# PCIe_USB.net
KiCad netlist of a schematic drawn in Altium Designer
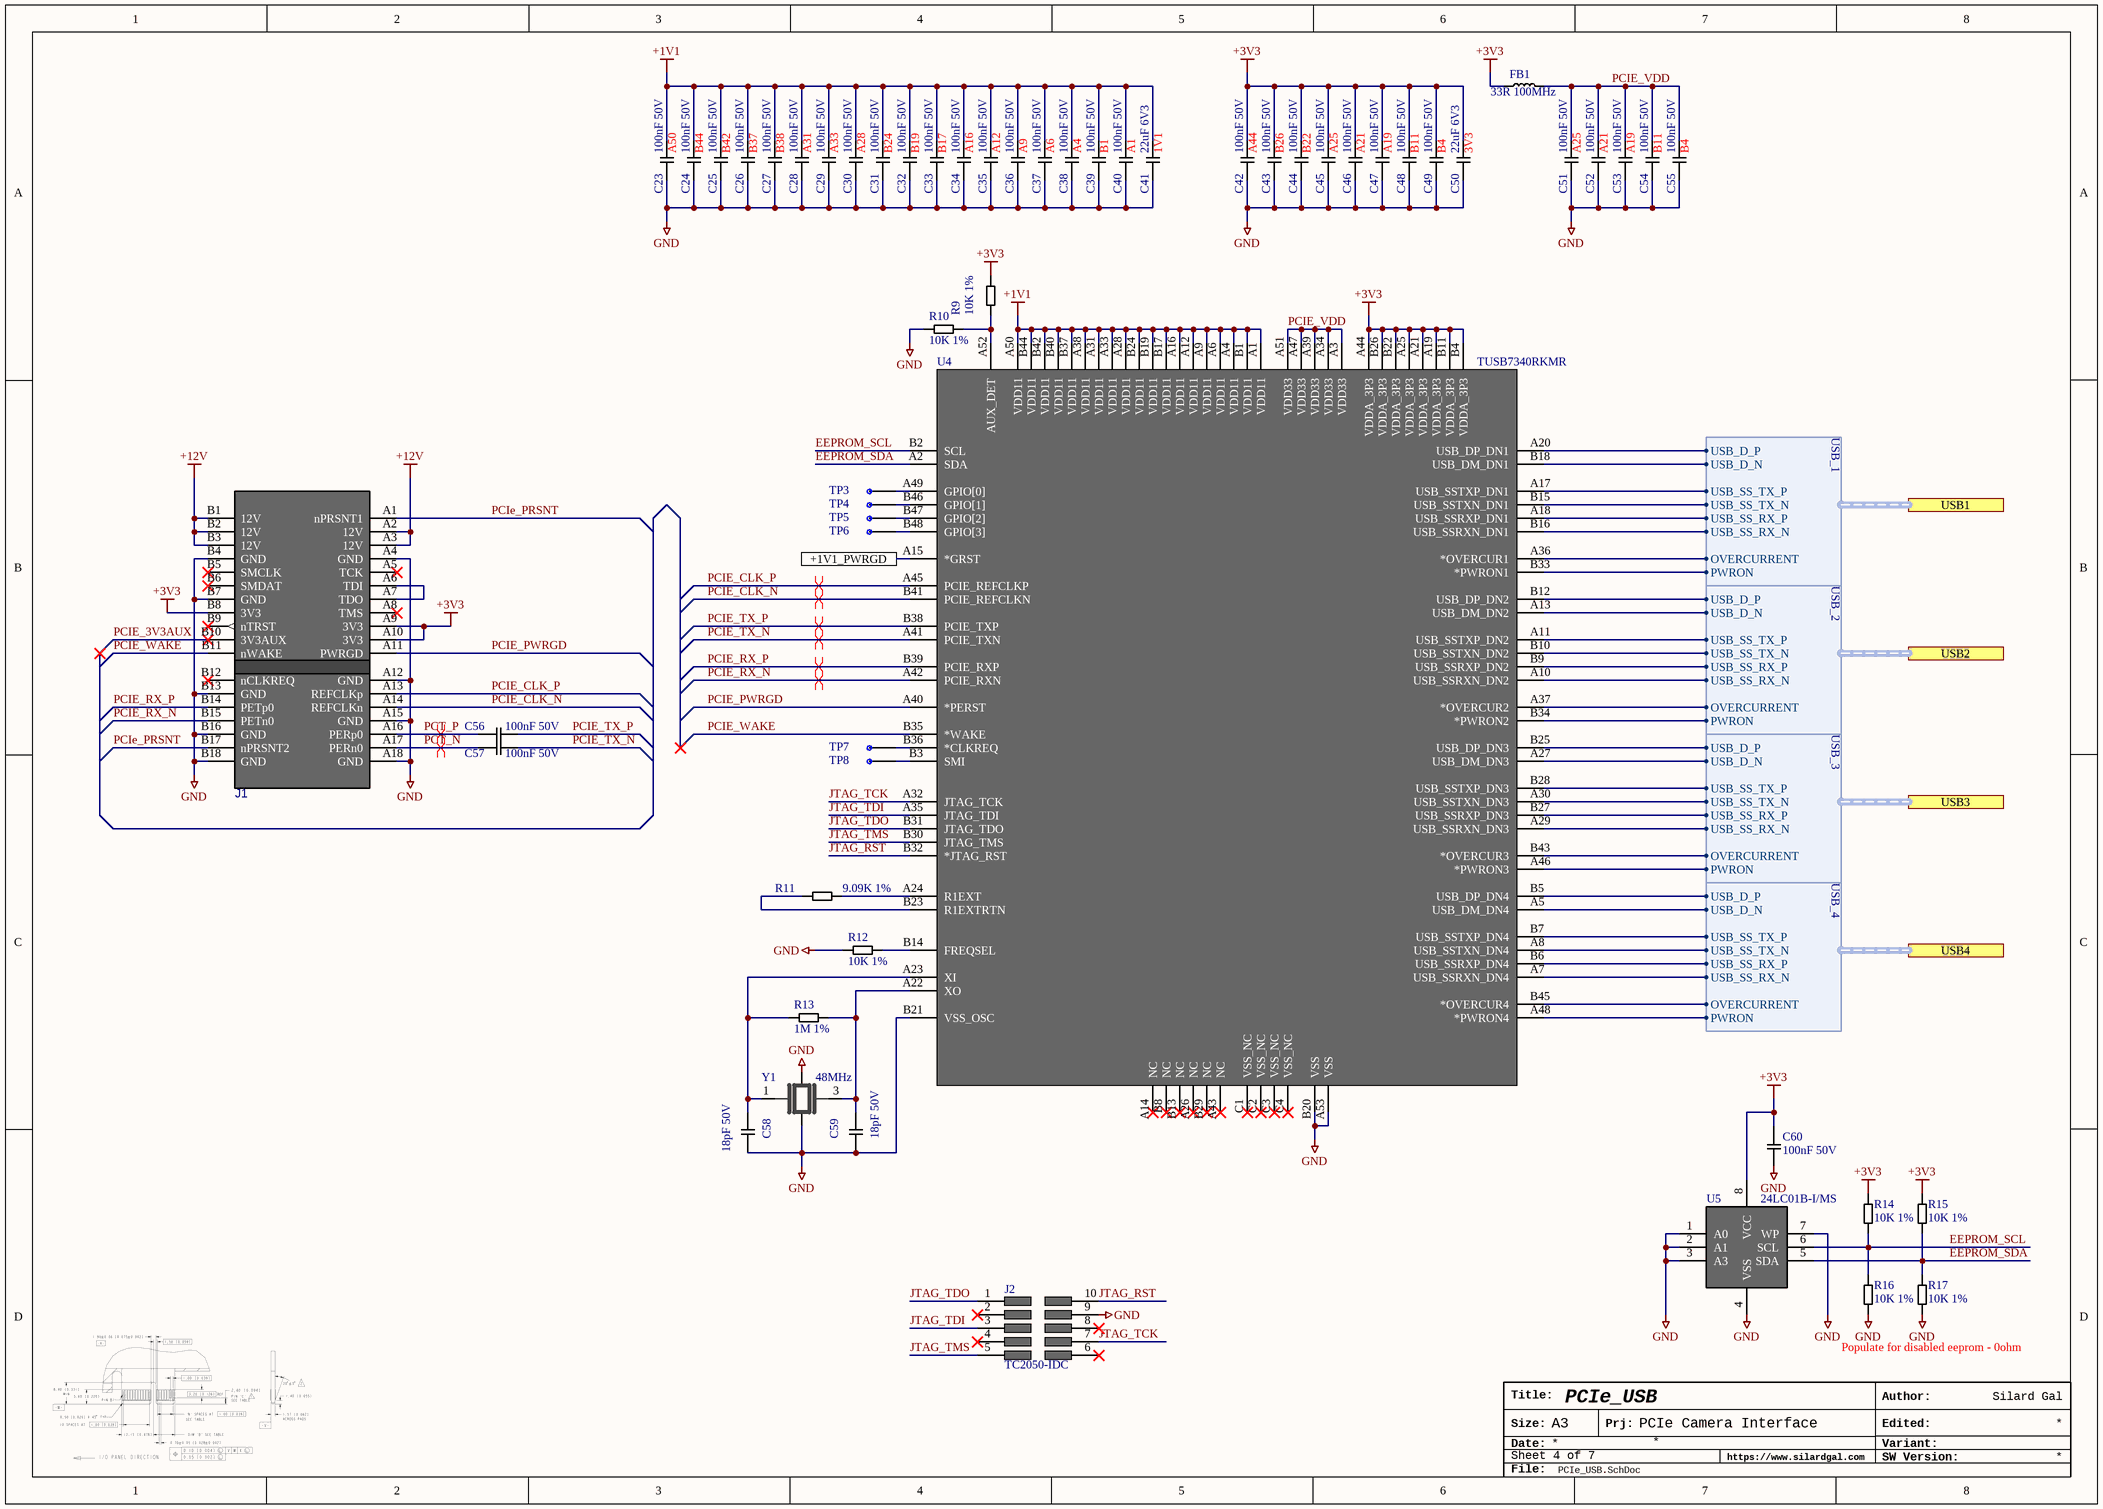
[diagram p0: PCIe_USB.SchDoc]

(export (version "E")
  (design (tool "Eeschema 10.0.6"))
  (components
    (comp (ref "C23")
      (value "100nF 50V")
      (footprint "CAPC1608X06N")
      (description "0.1 µF ±10% 50V Ceramic Capacitor X7R 0603 (1608 Metric)")
      (fields (field (name "MPN") "GCM188R71H104KA57D"))
      (libsource (lib "PCIe_Camera_Interface_Library") (part "100nF 50V"))
    )
    (comp (ref "C24")
      (value "100nF 50V")
      (footprint "CAPC1608X06N")
      (description "0.1 µF ±10% 50V Ceramic Capacitor X7R 0603 (1608 Metric)")
      (fields (field (name "MPN") "GCM188R71H104KA57D"))
      (libsource (lib "PCIe_Camera_Interface_Library") (part "100nF 50V"))
    )
    (comp (ref "C25")
      (value "100nF 50V")
      (footprint "CAPC1608X06N")
      (description "0.1 µF ±10% 50V Ceramic Capacitor X7R 0603 (1608 Metric)")
      (fields (field (name "MPN") "GCM188R71H104KA57D"))
      (libsource (lib "PCIe_Camera_Interface_Library") (part "100nF 50V"))
    )
    (comp (ref "C26")
      (value "100nF 50V")
      (footprint "CAPC1608X06N")
      (description "0.1 µF ±10% 50V Ceramic Capacitor X7R 0603 (1608 Metric)")
      (fields (field (name "MPN") "GCM188R71H104KA57D"))
      (libsource (lib "PCIe_Camera_Interface_Library") (part "100nF 50V"))
    )
    (comp (ref "C27")
      (value "100nF 50V")
      (footprint "CAPC1608X06N")
      (description "0.1 µF ±10% 50V Ceramic Capacitor X7R 0603 (1608 Metric)")
      (fields (field (name "MPN") "GCM188R71H104KA57D"))
      (libsource (lib "PCIe_Camera_Interface_Library") (part "100nF 50V"))
    )
    (comp (ref "C28")
      (value "100nF 50V")
      (footprint "CAPC1608X06N")
      (description "0.1 µF ±10% 50V Ceramic Capacitor X7R 0603 (1608 Metric)")
      (fields (field (name "MPN") "GCM188R71H104KA57D"))
      (libsource (lib "PCIe_Camera_Interface_Library") (part "100nF 50V"))
    )
    (comp (ref "C29")
      (value "100nF 50V")
      (footprint "CAPC1608X06N")
      (description "0.1 µF ±10% 50V Ceramic Capacitor X7R 0603 (1608 Metric)")
      (fields (field (name "MPN") "GCM188R71H104KA57D"))
      (libsource (lib "PCIe_Camera_Interface_Library") (part "100nF 50V"))
    )
    (comp (ref "C30")
      (value "100nF 50V")
      (footprint "CAPC1608X06N")
      (description "0.1 µF ±10% 50V Ceramic Capacitor X7R 0603 (1608 Metric)")
      (fields (field (name "MPN") "GCM188R71H104KA57D"))
      (libsource (lib "PCIe_Camera_Interface_Library") (part "100nF 50V"))
    )
    (comp (ref "C31")
      (value "100nF 50V")
      (footprint "CAPC1608X06N")
      (description "0.1 µF ±10% 50V Ceramic Capacitor X7R 0603 (1608 Metric)")
      (fields (field (name "MPN") "GCM188R71H104KA57D"))
      (libsource (lib "PCIe_Camera_Interface_Library") (part "100nF 50V"))
    )
    (comp (ref "C32")
      (value "100nF 50V")
      (footprint "CAPC1608X06N")
      (description "0.1 µF ±10% 50V Ceramic Capacitor X7R 0603 (1608 Metric)")
      (fields (field (name "MPN") "GCM188R71H104KA57D"))
      (libsource (lib "PCIe_Camera_Interface_Library") (part "100nF 50V"))
    )
    (comp (ref "C33")
      (value "100nF 50V")
      (footprint "CAPC1608X06N")
      (description "0.1 µF ±10% 50V Ceramic Capacitor X7R 0603 (1608 Metric)")
      (fields (field (name "MPN") "GCM188R71H104KA57D"))
      (libsource (lib "PCIe_Camera_Interface_Library") (part "100nF 50V"))
    )
    (comp (ref "C34")
      (value "100nF 50V")
      (footprint "CAPC1608X06N")
      (description "0.1 µF ±10% 50V Ceramic Capacitor X7R 0603 (1608 Metric)")
      (fields (field (name "MPN") "GCM188R71H104KA57D"))
      (libsource (lib "PCIe_Camera_Interface_Library") (part "100nF 50V"))
    )
    (comp (ref "C35")
      (value "100nF 50V")
      (footprint "CAPC1608X06N")
      (description "0.1 µF ±10% 50V Ceramic Capacitor X7R 0603 (1608 Metric)")
      (fields (field (name "MPN") "GCM188R71H104KA57D"))
      (libsource (lib "PCIe_Camera_Interface_Library") (part "100nF 50V"))
    )
    (comp (ref "C36")
      (value "100nF 50V")
      (footprint "CAPC1608X06N")
      (description "0.1 µF ±10% 50V Ceramic Capacitor X7R 0603 (1608 Metric)")
      (fields (field (name "MPN") "GCM188R71H104KA57D"))
      (libsource (lib "PCIe_Camera_Interface_Library") (part "100nF 50V"))
    )
    (comp (ref "C37")
      (value "100nF 50V")
      (footprint "CAPC1608X06N")
      (description "0.1 µF ±10% 50V Ceramic Capacitor X7R 0603 (1608 Metric)")
      (fields (field (name "MPN") "GCM188R71H104KA57D"))
      (libsource (lib "PCIe_Camera_Interface_Library") (part "100nF 50V"))
    )
    (comp (ref "C38")
      (value "100nF 50V")
      (footprint "CAPC1608X06N")
      (description "0.1 µF ±10% 50V Ceramic Capacitor X7R 0603 (1608 Metric)")
      (fields (field (name "MPN") "GCM188R71H104KA57D"))
      (libsource (lib "PCIe_Camera_Interface_Library") (part "100nF 50V"))
    )
    (comp (ref "C39")
      (value "100nF 50V")
      (footprint "CAPC1608X06N")
      (description "0.1 µF ±10% 50V Ceramic Capacitor X7R 0603 (1608 Metric)")
      (fields (field (name "MPN") "GCM188R71H104KA57D"))
      (libsource (lib "PCIe_Camera_Interface_Library") (part "100nF 50V"))
    )
    (comp (ref "C40")
      (value "100nF 50V")
      (footprint "CAPC1608X06N")
      (description "0.1 µF ±10% 50V Ceramic Capacitor X7R 0603 (1608 Metric)")
      (fields (field (name "MPN") "GCM188R71H104KA57D"))
      (libsource (lib "PCIe_Camera_Interface_Library") (part "100nF 50V"))
    )
    (comp (ref "C41")
      (value "22uF 6V3")
      (footprint "CAPC1608X06N")
      (description "22 µF ±20% 6.3V Ceramic Capacitor X5R 0603 (1608 Metric)")
      (fields (field (name "MPN") "GRM188R60J226MEA0D"))
      (libsource (lib "PCIe_Camera_Interface_Library") (part "22uF 6V3"))
    )
    (comp (ref "C42")
      (value "100nF 50V")
      (footprint "CAPC1608X06N")
      (description "0.1 µF ±10% 50V Ceramic Capacitor X7R 0603 (1608 Metric)")
      (fields (field (name "MPN") "GCM188R71H104KA57D"))
      (libsource (lib "PCIe_Camera_Interface_Library") (part "100nF 50V"))
    )
    (comp (ref "C43")
      (value "100nF 50V")
      (footprint "CAPC1608X06N")
      (description "0.1 µF ±10% 50V Ceramic Capacitor X7R 0603 (1608 Metric)")
      (fields (field (name "MPN") "GCM188R71H104KA57D"))
      (libsource (lib "PCIe_Camera_Interface_Library") (part "100nF 50V"))
    )
    (comp (ref "C44")
      (value "100nF 50V")
      (footprint "CAPC1608X06N")
      (description "0.1 µF ±10% 50V Ceramic Capacitor X7R 0603 (1608 Metric)")
      (fields (field (name "MPN") "GCM188R71H104KA57D"))
      (libsource (lib "PCIe_Camera_Interface_Library") (part "100nF 50V"))
    )
    (comp (ref "C45")
      (value "100nF 50V")
      (footprint "CAPC1608X06N")
      (description "0.1 µF ±10% 50V Ceramic Capacitor X7R 0603 (1608 Metric)")
      (fields (field (name "MPN") "GCM188R71H104KA57D"))
      (libsource (lib "PCIe_Camera_Interface_Library") (part "100nF 50V"))
    )
    (comp (ref "C46")
      (value "100nF 50V")
      (footprint "CAPC1608X06N")
      (description "0.1 µF ±10% 50V Ceramic Capacitor X7R 0603 (1608 Metric)")
      (fields (field (name "MPN") "GCM188R71H104KA57D"))
      (libsource (lib "PCIe_Camera_Interface_Library") (part "100nF 50V"))
    )
    (comp (ref "C47")
      (value "100nF 50V")
      (footprint "CAPC1608X06N")
      (description "0.1 µF ±10% 50V Ceramic Capacitor X7R 0603 (1608 Metric)")
      (fields (field (name "MPN") "GCM188R71H104KA57D"))
      (libsource (lib "PCIe_Camera_Interface_Library") (part "100nF 50V"))
    )
    (comp (ref "C48")
      (value "100nF 50V")
      (footprint "CAPC1608X06N")
      (description "0.1 µF ±10% 50V Ceramic Capacitor X7R 0603 (1608 Metric)")
      (fields (field (name "MPN") "GCM188R71H104KA57D"))
      (libsource (lib "PCIe_Camera_Interface_Library") (part "100nF 50V"))
    )
    (comp (ref "C49")
      (value "100nF 50V")
      (footprint "CAPC1608X06N")
      (description "0.1 µF ±10% 50V Ceramic Capacitor X7R 0603 (1608 Metric)")
      (fields (field (name "MPN") "GCM188R71H104KA57D"))
      (libsource (lib "PCIe_Camera_Interface_Library") (part "100nF 50V"))
    )
    (comp (ref "C50")
      (value "22uF 6V3")
      (footprint "CAPC1608X06N")
      (description "22 µF ±20% 6.3V Ceramic Capacitor X5R 0603 (1608 Metric)")
      (fields (field (name "MPN") "GRM188R60J226MEA0D"))
      (libsource (lib "PCIe_Camera_Interface_Library") (part "22uF 6V3"))
    )
    (comp (ref "C51")
      (value "100nF 50V")
      (footprint "CAPC1608X06N")
      (description "0.1 µF ±10% 50V Ceramic Capacitor X7R 0603 (1608 Metric)")
      (fields (field (name "MPN") "GCM188R71H104KA57D"))
      (libsource (lib "PCIe_Camera_Interface_Library") (part "100nF 50V"))
    )
    (comp (ref "C52")
      (value "100nF 50V")
      (footprint "CAPC1608X06N")
      (description "0.1 µF ±10% 50V Ceramic Capacitor X7R 0603 (1608 Metric)")
      (fields (field (name "MPN") "GCM188R71H104KA57D"))
      (libsource (lib "PCIe_Camera_Interface_Library") (part "100nF 50V"))
    )
    (comp (ref "C53")
      (value "100nF 50V")
      (footprint "CAPC1608X06N")
      (description "0.1 µF ±10% 50V Ceramic Capacitor X7R 0603 (1608 Metric)")
      (fields (field (name "MPN") "GCM188R71H104KA57D"))
      (libsource (lib "PCIe_Camera_Interface_Library") (part "100nF 50V"))
    )
    (comp (ref "C54")
      (value "100nF 50V")
      (footprint "CAPC1608X06N")
      (description "0.1 µF ±10% 50V Ceramic Capacitor X7R 0603 (1608 Metric)")
      (fields (field (name "MPN") "GCM188R71H104KA57D"))
      (libsource (lib "PCIe_Camera_Interface_Library") (part "100nF 50V"))
    )
    (comp (ref "C55")
      (value "100nF 50V")
      (footprint "CAPC1608X06N")
      (description "0.1 µF ±10% 50V Ceramic Capacitor X7R 0603 (1608 Metric)")
      (fields (field (name "MPN") "GCM188R71H104KA57D"))
      (libsource (lib "PCIe_Camera_Interface_Library") (part "100nF 50V"))
    )
    (comp (ref "C56")
      (value "100nF 50V")
      (footprint "CAPC1005X06N")
      (description "0.1 µF ±10% 16V Ceramic Capacitor X7R 0402 (1005 Metric)")
      (fields (field (name "MPN") "GRM155R71C104KA88J"))
      (libsource (lib "PCIe_Camera_Interface_Library") (part "100nF 50V_1"))
    )
    (comp (ref "C57")
      (value "100nF 50V")
      (footprint "CAPC1005X06N")
      (description "0.1 µF ±10% 16V Ceramic Capacitor X7R 0402 (1005 Metric)")
      (fields (field (name "MPN") "GRM155R71C104KA88J"))
      (libsource (lib "PCIe_Camera_Interface_Library") (part "100nF 50V_1"))
    )
    (comp (ref "C58")
      (value "18pF 50V")
      (footprint "CAPC1608X06N")
      (description "CAP CER 18PF 50V C0G/NP0 0603")
      (fields (field (name "MPN") "GRM1885C1H180JA01D"))
      (libsource (lib "PCIe_Camera_Interface_Library") (part "18pF 50V"))
    )
    (comp (ref "C59")
      (value "18pF 50V")
      (footprint "CAPC1608X06N")
      (description "CAP CER 18PF 50V C0G/NP0 0603")
      (fields (field (name "MPN") "GRM1885C1H180JA01D"))
      (libsource (lib "PCIe_Camera_Interface_Library") (part "18pF 50V"))
    )
    (comp (ref "C60")
      (value "100nF 50V")
      (footprint "CAPC1608X06N")
      (description "0.1 µF ±10% 50V Ceramic Capacitor X7R 0603 (1608 Metric)")
      (fields (field (name "MPN") "GCM188R71H104KA57D"))
      (libsource (lib "PCIe_Camera_Interface_Library") (part "100nF 50V"))
    )
    (comp (ref "FB1")
      (value "33R 100MHz")
      (footprint "INDC1608X06N")
      (description "33 Ohms @ 100 MHz 1 Power Line Ferrite Bead 0603 (1608 Metric) 3A 25mOhm")
      (fields (field (name "MPN") "BLM18PG330SN1D"))
      (libsource (lib "PCIe_Camera_Interface_Library") (part "33R 100MHz"))
    )
    (comp (ref "J1")
      (value "PCIe x1")
      (footprint "CON FINGERS PCIEx1 1mm 36P PCB")
      (description "Connector, PCB Edge, plug 2x18 positions, 1.0mm pitch")
      (libsource (lib "PCIe_Camera_Interface_Library") (part "CON_Edge_PCB_PCIe_x1_36P"))
    )
    (comp (ref "J2")
      (value "TC2050-IDC")
      (footprint "TAG_CONNECT")
      (libsource (lib "PCIe_Camera_Interface_Library") (part "TC2050-IDC"))
    )
    (comp (ref "R9")
      (value "10K 1%")
      (footprint "RESC1608X06N")
      (description "10 kOhms ±1% 0.1W, 1/10W Chip Resistor 0603 (1608 Metric) Automotive AEC-Q200 Thick Film")
      (fields (field (name "MPN") "ERJ-3EKF1002V"))
      (libsource (lib "PCIe_Camera_Interface_Library") (part "10K 1%"))
    )
    (comp (ref "R10")
      (value "10K 1%")
      (footprint "RESC1608X06N")
      (description "10 kOhms ±1% 0.1W, 1/10W Chip Resistor 0603 (1608 Metric) Automotive AEC-Q200 Thick Film")
      (fields (field (name "MPN") "ERJ-3EKF1002V"))
      (libsource (lib "PCIe_Camera_Interface_Library") (part "10K 1%"))
    )
    (comp (ref "R11")
      (value "9.09K 1%")
      (footprint "RESC1608X06N")
      (description "9.09 kOhms ±1% 0.1W, 1/10W Chip Resistor 0603 (1608 Metric) Automotive AEC-Q200 Thick Film")
      (fields (field (name "MPN") "ERJ-3EKF9091V"))
      (libsource (lib "PCIe_Camera_Interface_Library") (part "9.09K 1%"))
    )
    (comp (ref "R12")
      (value "10K 1%")
      (footprint "RESC1608X06N")
      (description "10 kOhms ±1% 0.1W, 1/10W Chip Resistor 0603 (1608 Metric) Automotive AEC-Q200 Thick Film")
      (fields (field (name "MPN") "ERJ-3EKF1002V"))
      (libsource (lib "PCIe_Camera_Interface_Library") (part "10K 1%"))
    )
    (comp (ref "R13")
      (value "1M 1%")
      (footprint "RESC1608X06N")
      (description "RES SMD 1M OHM 1% 1/10W 0603")
      (fields (field (name "MPN") "ERJ-3EKF1004V"))
      (libsource (lib "PCIe_Camera_Interface_Library") (part "1M 1%"))
    )
    (comp (ref "R14")
      (value "10K 1%")
      (footprint "RESC1608X06N")
      (description "10 kOhms ±1% 0.1W, 1/10W Chip Resistor 0603 (1608 Metric) Automotive AEC-Q200 Thick Film")
      (fields (field (name "MPN") "ERJ-3EKF1002V"))
      (libsource (lib "PCIe_Camera_Interface_Library") (part "10K 1%"))
    )
    (comp (ref "R15")
      (value "10K 1%")
      (footprint "RESC1608X06N")
      (description "10 kOhms ±1% 0.1W, 1/10W Chip Resistor 0603 (1608 Metric) Automotive AEC-Q200 Thick Film")
      (fields (field (name "MPN") "ERJ-3EKF1002V"))
      (libsource (lib "PCIe_Camera_Interface_Library") (part "10K 1%"))
    )
    (comp (ref "R16")
      (value "10K 1%")
      (footprint "RESC1608X06N")
      (description "10 kOhms ±1% 0.1W, 1/10W Chip Resistor 0603 (1608 Metric) Automotive AEC-Q200 Thick Film")
      (fields (field (name "MPN") "ERJ-3EKF1002V"))
      (libsource (lib "PCIe_Camera_Interface_Library") (part "10K 1%"))
    )
    (comp (ref "R17")
      (value "10K 1%")
      (footprint "RESC1608X06N")
      (description "10 kOhms ±1% 0.1W, 1/10W Chip Resistor 0603 (1608 Metric) Automotive AEC-Q200 Thick Film")
      (fields (field (name "MPN") "ERJ-3EKF1002V"))
      (libsource (lib "PCIe_Camera_Interface_Library") (part "10K 1%"))
    )
    (comp (ref "TP3")
      (value "TP")
      (footprint "TP")
      (libsource (lib "PCIe_Camera_Interface_Library") (part "TP"))
    )
    (comp (ref "TP4")
      (value "TP")
      (footprint "TP")
      (libsource (lib "PCIe_Camera_Interface_Library") (part "TP"))
    )
    (comp (ref "TP5")
      (value "TP")
      (footprint "TP")
      (libsource (lib "PCIe_Camera_Interface_Library") (part "TP"))
    )
    (comp (ref "TP6")
      (value "TP")
      (footprint "TP")
      (libsource (lib "PCIe_Camera_Interface_Library") (part "TP"))
    )
    (comp (ref "TP7")
      (value "TP")
      (footprint "TP")
      (libsource (lib "PCIe_Camera_Interface_Library") (part "TP"))
    )
    (comp (ref "TP8")
      (value "TP")
      (footprint "TP")
      (libsource (lib "PCIe_Camera_Interface_Library") (part "TP"))
    )
    (comp (ref "U4")
      (value "TUSB7340RKMR")
      (footprint "100-WQFN")
      (description "USB Host Controller USB 3.0 USB, PCIe Interface 100-WQFN-MR (9x9)")
      (libsource (lib "PCIe_Camera_Interface_Library") (part "TUSB7340RKMR"))
    )
    (comp (ref "U5")
      (value "24LC01B-I/MS")
      (footprint "SOP65P490X110-8N")
      (description "EEPROM Memory IC 1Kbit I2C 400 kHz 3.5 µs 8-MSOP")
      (libsource (lib "PCIe_Camera_Interface_Library") (part "24LC01B-I/MS"))
    )
    (comp (ref "Y1")
      (value "48MHz")
      (footprint "XTAL_ABM8G-48.000MHZ-18-D2Y-T")
      (description "48 MHz ±20ppm Crystal 18pF 50 Ohms 4-SMD, No Lead")
      (fields (field (name "MPN") "ABM8G-48.000MHZ-18-D2Y-T"))
      (libsource (lib "PCIe_Camera_Interface_Library") (part "ABM8G-48.000MHZ-18-D2Y-T"))
    )
  )
  (nets
    (net (code "5") (name "+1V1") (class "Default")
      (node (ref "C23") (pin "2") (pinfunction "2_2") (pintype "passive"))
      (node (ref "C24") (pin "2") (pinfunction "2_2") (pintype "passive"))
      (node (ref "C25") (pin "2") (pinfunction "2_2") (pintype "passive"))
      (node (ref "C26") (pin "2") (pinfunction "2_2") (pintype "passive"))
      (node (ref "C27") (pin "2") (pinfunction "2_2") (pintype "passive"))
      (node (ref "C28") (pin "2") (pinfunction "2_2") (pintype "passive"))
      (node (ref "C29") (pin "2") (pinfunction "2_2") (pintype "passive"))
      (node (ref "C30") (pin "2") (pinfunction "2_2") (pintype "passive"))
      (node (ref "C31") (pin "2") (pinfunction "2_2") (pintype "passive"))
      (node (ref "C32") (pin "2") (pinfunction "2_2") (pintype "passive"))
      (node (ref "C33") (pin "2") (pinfunction "2_2") (pintype "passive"))
      (node (ref "C34") (pin "2") (pinfunction "2_2") (pintype "passive"))
      (node (ref "C35") (pin "2") (pinfunction "2_2") (pintype "passive"))
      (node (ref "C36") (pin "2") (pinfunction "2_2") (pintype "passive"))
      (node (ref "C37") (pin "2") (pinfunction "2_2") (pintype "passive"))
      (node (ref "C38") (pin "2") (pinfunction "2_2") (pintype "passive"))
      (node (ref "C39") (pin "2") (pinfunction "2_2") (pintype "passive"))
      (node (ref "C40") (pin "2") (pinfunction "2_2") (pintype "passive"))
      (node (ref "C41") (pin "2") (pinfunction "2_2") (pintype "passive"))
      (node (ref "U4") (pin "A1") (pinfunction "VDD11_A1") (pintype "passive"))
      (node (ref "U4") (pin "A12") (pinfunction "VDD11_A12") (pintype "passive"))
      (node (ref "U4") (pin "A16") (pinfunction "VDD11_A16") (pintype "passive"))
      (node (ref "U4") (pin "A28") (pinfunction "VDD11_A28") (pintype "passive"))
      (node (ref "U4") (pin "A31") (pinfunction "VDD11_A31") (pintype "passive"))
      (node (ref "U4") (pin "A33") (pinfunction "VDD11_A33") (pintype "passive"))
      (node (ref "U4") (pin "A38") (pinfunction "VDD11_A38") (pintype "passive"))
      (node (ref "U4") (pin "A4") (pinfunction "VDD11_A4") (pintype "passive"))
      (node (ref "U4") (pin "A50") (pinfunction "VDD11_A50") (pintype "passive"))
      (node (ref "U4") (pin "A6") (pinfunction "VDD11_A6") (pintype "passive"))
      (node (ref "U4") (pin "A9") (pinfunction "VDD11_A9") (pintype "passive"))
      (node (ref "U4") (pin "B1") (pinfunction "VDD11_B1") (pintype "passive"))
      (node (ref "U4") (pin "B17") (pinfunction "VDD11_B17") (pintype "passive"))
      (node (ref "U4") (pin "B19") (pinfunction "VDD11_B19") (pintype "passive"))
      (node (ref "U4") (pin "B24") (pinfunction "VDD11_B24") (pintype "passive"))
      (node (ref "U4") (pin "B37") (pinfunction "VDD11_B37") (pintype "passive"))
      (node (ref "U4") (pin "B40") (pinfunction "VDD11_B40") (pintype "passive"))
      (node (ref "U4") (pin "B42") (pinfunction "VDD11_B42") (pintype "passive"))
      (node (ref "U4") (pin "B44") (pinfunction "VDD11_B44") (pintype "passive"))
    )
    (net (code "6") (name "+3V3") (class "Default")
      (node (ref "C42") (pin "2") (pinfunction "2_2") (pintype "passive"))
      (node (ref "C43") (pin "2") (pinfunction "2_2") (pintype "passive"))
      (node (ref "C44") (pin "2") (pinfunction "2_2") (pintype "passive"))
      (node (ref "C45") (pin "2") (pinfunction "2_2") (pintype "passive"))
      (node (ref "C46") (pin "2") (pinfunction "2_2") (pintype "passive"))
      (node (ref "C47") (pin "2") (pinfunction "2_2") (pintype "passive"))
      (node (ref "C48") (pin "2") (pinfunction "2_2") (pintype "passive"))
      (node (ref "C49") (pin "2") (pinfunction "2_2") (pintype "passive"))
      (node (ref "C50") (pin "2") (pinfunction "2_2") (pintype "passive"))
      (node (ref "C60") (pin "1") (pinfunction "1_1") (pintype "passive"))
      (node (ref "FB1") (pin "1") (pinfunction "1_1") (pintype "passive"))
      (node (ref "J1") (pin "A10") (pinfunction "3V3_A10") (pintype "power_in"))
      (node (ref "J1") (pin "A9") (pinfunction "3V3_A9") (pintype "power_in"))
      (node (ref "J1") (pin "B8") (pinfunction "3V3_B8") (pintype "power_in"))
      (node (ref "R14") (pin "1") (pinfunction "1_1") (pintype "passive"))
      (node (ref "R15") (pin "1") (pinfunction "1_1") (pintype "passive"))
      (node (ref "R9") (pin "2") (pinfunction "2_2") (pintype "passive"))
      (node (ref "U4") (pin "A19") (pinfunction "VDDA_3P3_A19") (pintype "passive"))
      (node (ref "U4") (pin "A21") (pinfunction "VDDA_3P3_A21") (pintype "passive"))
      (node (ref "U4") (pin "A25") (pinfunction "VDDA_3P3_A25") (pintype "passive"))
      (node (ref "U4") (pin "A44") (pinfunction "VDDA_3P3_A44") (pintype "passive"))
      (node (ref "U4") (pin "B11") (pinfunction "VDDA_3P3_B11") (pintype "passive"))
      (node (ref "U4") (pin "B22") (pinfunction "VDDA_3P3_B22") (pintype "passive"))
      (node (ref "U4") (pin "B26") (pinfunction "VDDA_3P3_B26") (pintype "passive"))
      (node (ref "U4") (pin "B4") (pinfunction "VDDA_3P3_B4") (pintype "passive"))
      (node (ref "U5") (pin "8") (pinfunction "VCC_8") (pintype "passive"))
    )
    (net (code "7") (name "+12V") (class "Default")
      (node (ref "J1") (pin "A2") (pinfunction "12V_A2") (pintype "power_in"))
      (node (ref "J1") (pin "A3") (pinfunction "12V_A3") (pintype "power_in"))
      (node (ref "J1") (pin "B1") (pinfunction "12V_B1") (pintype "power_in"))
      (node (ref "J1") (pin "B2") (pinfunction "12V_B2") (pintype "power_in"))
      (node (ref "J1") (pin "B3") (pinfunction "12V_B3") (pintype "power_in"))
    )
    (net (code "8") (name "/+1V1_PWRGD") (class "Default")
      (node (ref "U4") (pin "A15") (pinfunction "*GRST_A15") (pintype "passive"))
    )
    (net (code "9") (name "/EEPROM_SCL") (class "Default")
      (node (ref "R14") (pin "2") (pinfunction "2_2") (pintype "passive"))
      (node (ref "R16") (pin "1") (pinfunction "1_1") (pintype "passive"))
      (node (ref "U4") (pin "B2") (pinfunction "SCL_B2") (pintype "passive"))
      (node (ref "U5") (pin "6") (pinfunction "SCL_6") (pintype "passive"))
    )
    (net (code "10") (name "/EEPROM_SDA") (class "Default")
      (node (ref "R15") (pin "2") (pinfunction "2_2") (pintype "passive"))
      (node (ref "R17") (pin "1") (pinfunction "1_1") (pintype "passive"))
      (node (ref "U4") (pin "A2") (pinfunction "SDA_A2") (pintype "passive"))
      (node (ref "U5") (pin "5") (pinfunction "SDA_5") (pintype "passive"))
    )
    (net (code "11") (name "/JTAG_RST") (class "Default")
      (node (ref "J2") (pin "10") (pinfunction "10_10") (pintype "passive"))
      (node (ref "U4") (pin "B32") (pinfunction "*JTAG_RST_B32") (pintype "passive"))
    )
    (net (code "12") (name "/JTAG_TCK") (class "Default")
      (node (ref "J2") (pin "7") (pinfunction "7_7") (pintype "passive"))
      (node (ref "U4") (pin "A32") (pinfunction "JTAG_TCK_A32") (pintype "passive"))
    )
    (net (code "13") (name "/JTAG_TDI") (class "Default")
      (node (ref "J2") (pin "3") (pinfunction "3_3") (pintype "passive"))
      (node (ref "U4") (pin "A35") (pinfunction "JTAG_TDI_A35") (pintype "passive"))
    )
    (net (code "14") (name "/JTAG_TDO") (class "Default")
      (node (ref "J2") (pin "1") (pinfunction "1_1") (pintype "passive"))
      (node (ref "U4") (pin "B31") (pinfunction "JTAG_TDO_B31") (pintype "passive"))
    )
    (net (code "15") (name "/JTAG_TMS") (class "Default")
      (node (ref "J2") (pin "5") (pinfunction "5_5") (pintype "passive"))
      (node (ref "U4") (pin "B30") (pinfunction "JTAG_TMS_B30") (pintype "passive"))
    )
    (net (code "16") (name "/PCIE_3V3AUX") (class "Default")
      (node (ref "J1") (pin "B10") (pinfunction "3V3AUX_B10") (pintype "passive+no_connect"))
    )
    (net (code "17") (name "/PCIE_CLK_N") (class "Default")
      (node (ref "J1") (pin "A14") (pinfunction "REFCLKn_A14") (pintype "passive"))
      (node (ref "U4") (pin "B41") (pinfunction "PCIE_REFCLKN_B41") (pintype "passive"))
    )
    (net (code "18") (name "/PCIE_CLK_P") (class "Default")
      (node (ref "J1") (pin "A13") (pinfunction "REFCLKp_A13") (pintype "passive"))
      (node (ref "U4") (pin "A45") (pinfunction "PCIE_REFCLKP_A45") (pintype "passive"))
    )
    (net (code "19") (name "/PCIE_PWRGD") (class "Default")
      (node (ref "J1") (pin "A11") (pinfunction "PWRGD_A11") (pintype "passive"))
      (node (ref "U4") (pin "A40") (pinfunction "*PERST_A40") (pintype "passive"))
    )
    (net (code "20") (name "/PCIE_RX_N") (class "Default")
      (node (ref "J1") (pin "B15") (pinfunction "PETn0_B15") (pintype "passive"))
      (node (ref "U4") (pin "A42") (pinfunction "PCIE_RXN_A42") (pintype "passive"))
    )
    (net (code "21") (name "/PCIE_RX_P") (class "Default")
      (node (ref "J1") (pin "B14") (pinfunction "PETp0_B14") (pintype "passive"))
      (node (ref "U4") (pin "B39") (pinfunction "PCIE_RXP_B39") (pintype "passive"))
    )
    (net (code "22") (name "/PCIE_TX_N") (class "Default")
      (node (ref "C57") (pin "2") (pinfunction "2_2") (pintype "passive"))
      (node (ref "U4") (pin "A41") (pinfunction "PCIE_TXN_A41") (pintype "passive"))
    )
    (net (code "23") (name "/PCIE_TX_P") (class "Default")
      (node (ref "C56") (pin "2") (pinfunction "2_2") (pintype "passive"))
      (node (ref "U4") (pin "B38") (pinfunction "PCIE_TXP_B38") (pintype "passive"))
    )
    (net (code "24") (name "/PCIE_VDD") (class "Default")
      (node (ref "C51") (pin "2") (pinfunction "2_2") (pintype "passive"))
      (node (ref "C52") (pin "2") (pinfunction "2_2") (pintype "passive"))
      (node (ref "C53") (pin "2") (pinfunction "2_2") (pintype "passive"))
      (node (ref "C54") (pin "2") (pinfunction "2_2") (pintype "passive"))
      (node (ref "C55") (pin "2") (pinfunction "2_2") (pintype "passive"))
      (node (ref "FB1") (pin "2") (pinfunction "2_2") (pintype "passive"))
      (node (ref "U4") (pin "A3") (pinfunction "VDD33_A3") (pintype "passive"))
      (node (ref "U4") (pin "A34") (pinfunction "VDD33_A34") (pintype "passive"))
      (node (ref "U4") (pin "A39") (pinfunction "VDD33_A39") (pintype "passive"))
      (node (ref "U4") (pin "A47") (pinfunction "VDD33_A47") (pintype "passive"))
      (node (ref "U4") (pin "A51") (pinfunction "VDD33_A51") (pintype "passive"))
    )
    (net (code "25") (name "/PCIE_WAKE") (class "Default")
      (node (ref "J1") (pin "B11") (pinfunction "nWAKE_B11") (pintype "passive"))
      (node (ref "U4") (pin "B35") (pinfunction "*WAKE_B35") (pintype "passive"))
    )
    (net (code "26") (name "/PCIe_PRSNT") (class "Default")
      (node (ref "J1") (pin "A1") (pinfunction "nPRSNT1_A1") (pintype "passive"))
      (node (ref "J1") (pin "B17") (pinfunction "nPRSNT2_B17") (pintype "passive"))
    )
    (net (code "27") (name "/PCT_N") (class "Default")
      (node (ref "C57") (pin "1") (pinfunction "1_1") (pintype "passive"))
      (node (ref "J1") (pin "A17") (pinfunction "PERn0_A17") (pintype "passive"))
    )
    (net (code "28") (name "/PCT_P") (class "Default")
      (node (ref "C56") (pin "1") (pinfunction "1_1") (pintype "passive"))
      (node (ref "J1") (pin "A16") (pinfunction "PERp0_A16") (pintype "passive"))
    )
    (net (code "33") (name "GND") (class "Default")
      (node (ref "C23") (pin "1") (pinfunction "1_1") (pintype "passive"))
      (node (ref "C24") (pin "1") (pinfunction "1_1") (pintype "passive"))
      (node (ref "C25") (pin "1") (pinfunction "1_1") (pintype "passive"))
      (node (ref "C26") (pin "1") (pinfunction "1_1") (pintype "passive"))
      (node (ref "C27") (pin "1") (pinfunction "1_1") (pintype "passive"))
      (node (ref "C28") (pin "1") (pinfunction "1_1") (pintype "passive"))
      (node (ref "C29") (pin "1") (pinfunction "1_1") (pintype "passive"))
      (node (ref "C30") (pin "1") (pinfunction "1_1") (pintype "passive"))
      (node (ref "C31") (pin "1") (pinfunction "1_1") (pintype "passive"))
      (node (ref "C32") (pin "1") (pinfunction "1_1") (pintype "passive"))
      (node (ref "C33") (pin "1") (pinfunction "1_1") (pintype "passive"))
      (node (ref "C34") (pin "1") (pinfunction "1_1") (pintype "passive"))
      (node (ref "C35") (pin "1") (pinfunction "1_1") (pintype "passive"))
      (node (ref "C36") (pin "1") (pinfunction "1_1") (pintype "passive"))
      (node (ref "C37") (pin "1") (pinfunction "1_1") (pintype "passive"))
      (node (ref "C38") (pin "1") (pinfunction "1_1") (pintype "passive"))
      (node (ref "C39") (pin "1") (pinfunction "1_1") (pintype "passive"))
      (node (ref "C40") (pin "1") (pinfunction "1_1") (pintype "passive"))
      (node (ref "C41") (pin "1") (pinfunction "1_1") (pintype "passive"))
      (node (ref "C42") (pin "1") (pinfunction "1_1") (pintype "passive"))
      (node (ref "C43") (pin "1") (pinfunction "1_1") (pintype "passive"))
      (node (ref "C44") (pin "1") (pinfunction "1_1") (pintype "passive"))
      (node (ref "C45") (pin "1") (pinfunction "1_1") (pintype "passive"))
      (node (ref "C46") (pin "1") (pinfunction "1_1") (pintype "passive"))
      (node (ref "C47") (pin "1") (pinfunction "1_1") (pintype "passive"))
      (node (ref "C48") (pin "1") (pinfunction "1_1") (pintype "passive"))
      (node (ref "C49") (pin "1") (pinfunction "1_1") (pintype "passive"))
      (node (ref "C50") (pin "1") (pinfunction "1_1") (pintype "passive"))
      (node (ref "C51") (pin "1") (pinfunction "1_1") (pintype "passive"))
      (node (ref "C52") (pin "1") (pinfunction "1_1") (pintype "passive"))
      (node (ref "C53") (pin "1") (pinfunction "1_1") (pintype "passive"))
      (node (ref "C54") (pin "1") (pinfunction "1_1") (pintype "passive"))
      (node (ref "C55") (pin "1") (pinfunction "1_1") (pintype "passive"))
      (node (ref "C58") (pin "1") (pinfunction "1_1") (pintype "passive"))
      (node (ref "C59") (pin "1") (pinfunction "1_1") (pintype "passive"))
      (node (ref "C60") (pin "2") (pinfunction "2_2") (pintype "passive"))
      (node (ref "J1") (pin "A12") (pinfunction "GND_A12") (pintype "power_in"))
      (node (ref "J1") (pin "A15") (pinfunction "GND_A15") (pintype "power_in"))
      (node (ref "J1") (pin "A18") (pinfunction "GND_A18") (pintype "power_in"))
      (node (ref "J1") (pin "A4") (pinfunction "GND_A4") (pintype "power_in"))
      (node (ref "J1") (pin "B13") (pinfunction "GND_B13") (pintype "power_in"))
      (node (ref "J1") (pin "B16") (pinfunction "GND_B16") (pintype "power_in"))
      (node (ref "J1") (pin "B18") (pinfunction "GND_B18") (pintype "power_in"))
      (node (ref "J1") (pin "B4") (pinfunction "GND_B4") (pintype "power_in"))
      (node (ref "J1") (pin "B7") (pinfunction "GND_B7") (pintype "power_in"))
      (node (ref "J2") (pin "9") (pinfunction "9_9") (pintype "passive"))
      (node (ref "R10") (pin "2") (pinfunction "2_2") (pintype "passive"))
      (node (ref "R12") (pin "2") (pinfunction "2_2") (pintype "passive"))
      (node (ref "R16") (pin "2") (pinfunction "2_2") (pintype "passive"))
      (node (ref "R17") (pin "2") (pinfunction "2_2") (pintype "passive"))
      (node (ref "U4") (pin "A53") (pinfunction "VSS_A53") (pintype "passive"))
      (node (ref "U4") (pin "B20") (pinfunction "VSS_B20") (pintype "passive"))
      (node (ref "U4") (pin "B21") (pinfunction "VSS_OSC_B21") (pintype "passive"))
      (node (ref "U5") (pin "1") (pinfunction "A0_1") (pintype "passive"))
      (node (ref "U5") (pin "2") (pinfunction "A1_2") (pintype "passive"))
      (node (ref "U5") (pin "3") (pinfunction "A3_3") (pintype "passive"))
      (node (ref "U5") (pin "4") (pinfunction "VSS_4") (pintype "passive"))
      (node (ref "U5") (pin "7") (pinfunction "WP_7") (pintype "passive"))
      (node (ref "Y1") (pin "2") (pinfunction "GND_2") (pintype "power_in"))
      (node (ref "Y1") (pin "4") (pinfunction "GND_4") (pintype "power_in"))
    )
    (net (code "34") (name "Net-(J1-TDI)") (class "Default")
      (node (ref "J1") (pin "A6") (pinfunction "TDI_A6") (pintype "passive"))
      (node (ref "J1") (pin "A7") (pinfunction "TDO_A7") (pintype "passive"))
    )
    (net (code "35") (name "Net-(U4-*CLKREQ)") (class "Default")
      (node (ref "TP7") (pin "1") (pinfunction "1_1") (pintype "passive"))
      (node (ref "U4") (pin "B36") (pinfunction "*CLKREQ_B36") (pintype "passive"))
    )
    (net (code "36") (name "Net-(U4-AUX_DET)") (class "Default")
      (node (ref "R10") (pin "1") (pinfunction "1_1") (pintype "passive"))
      (node (ref "R9") (pin "1") (pinfunction "1_1") (pintype "passive"))
      (node (ref "U4") (pin "A52") (pinfunction "AUX_DET_A52") (pintype "passive"))
    )
    (net (code "37") (name "Net-(U4-FREQSEL)") (class "Default")
      (node (ref "R12") (pin "1") (pinfunction "1_1") (pintype "passive"))
      (node (ref "U4") (pin "B14") (pinfunction "FREQSEL_B14") (pintype "passive"))
    )
    (net (code "38") (name "Net-(U4-GPIO[0])") (class "Default")
      (node (ref "TP3") (pin "1") (pinfunction "1_1") (pintype "passive"))
      (node (ref "U4") (pin "A49") (pinfunction "GPIO[0]_A49") (pintype "passive"))
    )
    (net (code "39") (name "Net-(U4-GPIO[1])") (class "Default")
      (node (ref "TP4") (pin "1") (pinfunction "1_1") (pintype "passive"))
      (node (ref "U4") (pin "B46") (pinfunction "GPIO[1]_B46") (pintype "passive"))
    )
    (net (code "40") (name "Net-(U4-GPIO[2])") (class "Default")
      (node (ref "TP5") (pin "1") (pinfunction "1_1") (pintype "passive"))
      (node (ref "U4") (pin "B47") (pinfunction "GPIO[2]_B47") (pintype "passive"))
    )
    (net (code "41") (name "Net-(U4-GPIO[3])") (class "Default")
      (node (ref "TP6") (pin "1") (pinfunction "1_1") (pintype "passive"))
      (node (ref "U4") (pin "B48") (pinfunction "GPIO[3]_B48") (pintype "passive"))
    )
    (net (code "42") (name "Net-(U4-R1EXT)") (class "Default")
      (node (ref "R11") (pin "2") (pinfunction "2_2") (pintype "passive"))
      (node (ref "U4") (pin "A24") (pinfunction "R1EXT_A24") (pintype "passive"))
    )
    (net (code "43") (name "Net-(U4-R1EXTRTN)") (class "Default")
      (node (ref "R11") (pin "1") (pinfunction "1_1") (pintype "passive"))
      (node (ref "U4") (pin "B23") (pinfunction "R1EXTRTN_B23") (pintype "passive"))
    )
    (net (code "44") (name "Net-(U4-SMI)") (class "Default")
      (node (ref "TP8") (pin "1") (pinfunction "1_1") (pintype "passive"))
      (node (ref "U4") (pin "B3") (pinfunction "SMI_B3") (pintype "passive"))
    )
    (net (code "45") (name "Net-(U4-XI)") (class "Default")
      (node (ref "C58") (pin "2") (pinfunction "2_2") (pintype "passive"))
      (node (ref "R13") (pin "1") (pinfunction "1_1") (pintype "passive"))
      (node (ref "U4") (pin "A23") (pinfunction "XI_A23") (pintype "passive"))
      (node (ref "Y1") (pin "1") (pinfunction "1_1") (pintype "passive"))
    )
    (net (code "46") (name "Net-(U4-XO)") (class "Default")
      (node (ref "C59") (pin "2") (pinfunction "2_2") (pintype "passive"))
      (node (ref "R13") (pin "2") (pinfunction "2_2") (pintype "passive"))
      (node (ref "U4") (pin "A22") (pinfunction "XO_A22") (pintype "passive"))
      (node (ref "Y1") (pin "3") (pinfunction "2_3") (pintype "passive"))
    )
    (net (code "47") (name "unconnected-(J1-SMCLK-PadB5)") (class "Default")
      (node (ref "J1") (pin "B5") (pinfunction "SMCLK_B5") (pintype "passive+no_connect"))
    )
    (net (code "48") (name "unconnected-(J1-SMDAT-PadB6)") (class "Default")
      (node (ref "J1") (pin "B6") (pinfunction "SMDAT_B6") (pintype "passive+no_connect"))
    )
    (net (code "49") (name "unconnected-(J1-TCK-PadA5)") (class "Default")
      (node (ref "J1") (pin "A5") (pinfunction "TCK_A5") (pintype "passive+no_connect"))
    )
    (net (code "50") (name "unconnected-(J1-TMS-PadA8)") (class "Default")
      (node (ref "J1") (pin "A8") (pinfunction "TMS_A8") (pintype "passive+no_connect"))
    )
    (net (code "51") (name "unconnected-(J1-nCLKREQ-PadB12)") (class "Default")
      (node (ref "J1") (pin "B12") (pinfunction "nCLKREQ_B12") (pintype "passive+no_connect"))
    )
    (net (code "52") (name "unconnected-(J1-nTRST-PadB9)") (class "Default")
      (node (ref "J1") (pin "B9") (pinfunction "nTRST_B9") (pintype "output+no_connect"))
    )
    (net (code "53") (name "unconnected-(J2-Pad2)") (class "Default")
      (node (ref "J2") (pin "2") (pinfunction "2_2") (pintype "passive+no_connect"))
    )
    (net (code "54") (name "unconnected-(J2-Pad4)") (class "Default")
      (node (ref "J2") (pin "4") (pinfunction "4_4") (pintype "passive+no_connect"))
    )
    (net (code "55") (name "unconnected-(J2-Pad6)") (class "Default")
      (node (ref "J2") (pin "6") (pinfunction "6_6") (pintype "passive+no_connect"))
    )
    (net (code "56") (name "unconnected-(J2-Pad8)") (class "Default")
      (node (ref "J2") (pin "8") (pinfunction "8_8") (pintype "passive+no_connect"))
    )
    (net (code "57") (name "unconnected-(U4-*OVERCUR1-PadA36)") (class "Default")
      (node (ref "U4") (pin "A36") (pinfunction "*OVERCUR1_A36") (pintype "passive"))
    )
    (net (code "58") (name "unconnected-(U4-*OVERCUR2-PadA37)") (class "Default")
      (node (ref "U4") (pin "A37") (pinfunction "*OVERCUR2_A37") (pintype "passive"))
    )
    (net (code "59") (name "unconnected-(U4-*OVERCUR3-PadB43)") (class "Default")
      (node (ref "U4") (pin "B43") (pinfunction "*OVERCUR3_B43") (pintype "passive"))
    )
    (net (code "60") (name "unconnected-(U4-*OVERCUR4-PadB45)") (class "Default")
      (node (ref "U4") (pin "B45") (pinfunction "*OVERCUR4_B45") (pintype "passive"))
    )
    (net (code "61") (name "unconnected-(U4-*PWRON1-PadB33)") (class "Default")
      (node (ref "U4") (pin "B33") (pinfunction "*PWRON1_B33") (pintype "passive"))
    )
    (net (code "62") (name "unconnected-(U4-*PWRON2-PadB34)") (class "Default")
      (node (ref "U4") (pin "B34") (pinfunction "*PWRON2_B34") (pintype "passive"))
    )
    (net (code "63") (name "unconnected-(U4-*PWRON3-PadA46)") (class "Default")
      (node (ref "U4") (pin "A46") (pinfunction "*PWRON3_A46") (pintype "passive"))
    )
    (net (code "64") (name "unconnected-(U4-*PWRON4-PadA48)") (class "Default")
      (node (ref "U4") (pin "A48") (pinfunction "*PWRON4_A48") (pintype "passive"))
    )
    (net (code "65") (name "unconnected-(U4-NC-PadA14)") (class "Default")
      (node (ref "U4") (pin "A14") (pinfunction "NC_A14") (pintype "passive+no_connect"))
    )
    (net (code "66") (name "unconnected-(U4-NC-PadA26)") (class "Default")
      (node (ref "U4") (pin "A26") (pinfunction "NC_A26") (pintype "passive+no_connect"))
    )
    (net (code "67") (name "unconnected-(U4-NC-PadA43)") (class "Default")
      (node (ref "U4") (pin "A43") (pinfunction "NC_A43") (pintype "passive+no_connect"))
    )
    (net (code "68") (name "unconnected-(U4-NC-PadB8)") (class "Default")
      (node (ref "U4") (pin "B8") (pinfunction "NC_B8") (pintype "passive+no_connect"))
    )
    (net (code "69") (name "unconnected-(U4-NC-PadB13)") (class "Default")
      (node (ref "U4") (pin "B13") (pinfunction "NC_B13") (pintype "passive+no_connect"))
    )
    (net (code "70") (name "unconnected-(U4-NC-PadB29)") (class "Default")
      (node (ref "U4") (pin "B29") (pinfunction "NC_B29") (pintype "passive+no_connect"))
    )
    (net (code "71") (name "unconnected-(U4-USB_DM_DN1-PadB18)") (class "Default")
      (node (ref "U4") (pin "B18") (pinfunction "USB_DM_DN1_B18") (pintype "passive"))
    )
    (net (code "72") (name "unconnected-(U4-USB_DM_DN2-PadA13)") (class "Default")
      (node (ref "U4") (pin "A13") (pinfunction "USB_DM_DN2_A13") (pintype "passive"))
    )
    (net (code "73") (name "unconnected-(U4-USB_DM_DN3-PadA27)") (class "Default")
      (node (ref "U4") (pin "A27") (pinfunction "USB_DM_DN3_A27") (pintype "passive"))
    )
    (net (code "74") (name "unconnected-(U4-USB_DM_DN4-PadA5)") (class "Default")
      (node (ref "U4") (pin "A5") (pinfunction "USB_DM_DN4_A5") (pintype "passive"))
    )
    (net (code "75") (name "unconnected-(U4-USB_DP_DN1-PadA20)") (class "Default")
      (node (ref "U4") (pin "A20") (pinfunction "USB_DP_DN1_A20") (pintype "passive"))
    )
    (net (code "76") (name "unconnected-(U4-USB_DP_DN2-PadB12)") (class "Default")
      (node (ref "U4") (pin "B12") (pinfunction "USB_DP_DN2_B12") (pintype "passive"))
    )
    (net (code "77") (name "unconnected-(U4-USB_DP_DN3-PadB25)") (class "Default")
      (node (ref "U4") (pin "B25") (pinfunction "USB_DP_DN3_B25") (pintype "passive"))
    )
    (net (code "78") (name "unconnected-(U4-USB_DP_DN4-PadB5)") (class "Default")
      (node (ref "U4") (pin "B5") (pinfunction "USB_DP_DN4_B5") (pintype "passive"))
    )
    (net (code "79") (name "unconnected-(U4-USB_SSRXN_DN1-PadB16)") (class "Default")
      (node (ref "U4") (pin "B16") (pinfunction "USB_SSRXN_DN1_B16") (pintype "passive"))
    )
    (net (code "80") (name "unconnected-(U4-USB_SSRXN_DN2-PadA10)") (class "Default")
      (node (ref "U4") (pin "A10") (pinfunction "USB_SSRXN_DN2_A10") (pintype "passive"))
    )
    (net (code "81") (name "unconnected-(U4-USB_SSRXN_DN3-PadA29)") (class "Default")
      (node (ref "U4") (pin "A29") (pinfunction "USB_SSRXN_DN3_A29") (pintype "passive"))
    )
    (net (code "82") (name "unconnected-(U4-USB_SSRXN_DN4-PadA7)") (class "Default")
      (node (ref "U4") (pin "A7") (pinfunction "USB_SSRXN_DN4_A7") (pintype "passive"))
    )
    (net (code "83") (name "unconnected-(U4-USB_SSRXP_DN1-PadA18)") (class "Default")
      (node (ref "U4") (pin "A18") (pinfunction "USB_SSRXP_DN1_A18") (pintype "passive"))
    )
    (net (code "84") (name "unconnected-(U4-USB_SSRXP_DN2-PadB9)") (class "Default")
      (node (ref "U4") (pin "B9") (pinfunction "USB_SSRXP_DN2_B9") (pintype "passive"))
    )
    (net (code "85") (name "unconnected-(U4-USB_SSRXP_DN3-PadB27)") (class "Default")
      (node (ref "U4") (pin "B27") (pinfunction "USB_SSRXP_DN3_B27") (pintype "passive"))
    )
    (net (code "86") (name "unconnected-(U4-USB_SSRXP_DN4-PadB6)") (class "Default")
      (node (ref "U4") (pin "B6") (pinfunction "USB_SSRXP_DN4_B6") (pintype "passive"))
    )
    (net (code "87") (name "unconnected-(U4-USB_SSTXN_DN1-PadB15)") (class "Default")
      (node (ref "U4") (pin "B15") (pinfunction "USB_SSTXN_DN1_B15") (pintype "passive"))
    )
    (net (code "88") (name "unconnected-(U4-USB_SSTXN_DN2-PadB10)") (class "Default")
      (node (ref "U4") (pin "B10") (pinfunction "USB_SSTXN_DN2_B10") (pintype "passive"))
    )
    (net (code "89") (name "unconnected-(U4-USB_SSTXN_DN3-PadA30)") (class "Default")
      (node (ref "U4") (pin "A30") (pinfunction "USB_SSTXN_DN3_A30") (pintype "passive"))
    )
    (net (code "90") (name "unconnected-(U4-USB_SSTXN_DN4-PadA8)") (class "Default")
      (node (ref "U4") (pin "A8") (pinfunction "USB_SSTXN_DN4_A8") (pintype "passive"))
    )
    (net (code "91") (name "unconnected-(U4-USB_SSTXP_DN1-PadA17)") (class "Default")
      (node (ref "U4") (pin "A17") (pinfunction "USB_SSTXP_DN1_A17") (pintype "passive"))
    )
    (net (code "92") (name "unconnected-(U4-USB_SSTXP_DN2-PadA11)") (class "Default")
      (node (ref "U4") (pin "A11") (pinfunction "USB_SSTXP_DN2_A11") (pintype "passive"))
    )
    (net (code "93") (name "unconnected-(U4-USB_SSTXP_DN3-PadB28)") (class "Default")
      (node (ref "U4") (pin "B28") (pinfunction "USB_SSTXP_DN3_B28") (pintype "passive"))
    )
    (net (code "94") (name "unconnected-(U4-USB_SSTXP_DN4-PadB7)") (class "Default")
      (node (ref "U4") (pin "B7") (pinfunction "USB_SSTXP_DN4_B7") (pintype "passive"))
    )
    (net (code "95") (name "unconnected-(U4-VSS_NC-PadC1)") (class "Default")
      (node (ref "U4") (pin "C1") (pinfunction "VSS_NC_C1") (pintype "passive+no_connect"))
    )
    (net (code "96") (name "unconnected-(U4-VSS_NC-PadC2)") (class "Default")
      (node (ref "U4") (pin "C2") (pinfunction "VSS_NC_C2") (pintype "passive+no_connect"))
    )
    (net (code "97") (name "unconnected-(U4-VSS_NC-PadC3)") (class "Default")
      (node (ref "U4") (pin "C3") (pinfunction "VSS_NC_C3") (pintype "passive+no_connect"))
    )
    (net (code "98") (name "unconnected-(U4-VSS_NC-PadC4)") (class "Default")
      (node (ref "U4") (pin "C4") (pinfunction "VSS_NC_C4") (pintype "passive+no_connect"))
    )
  )
)
